# External_Power_Supply.net
KiCad netlist of a schematic drawn in EAGLE
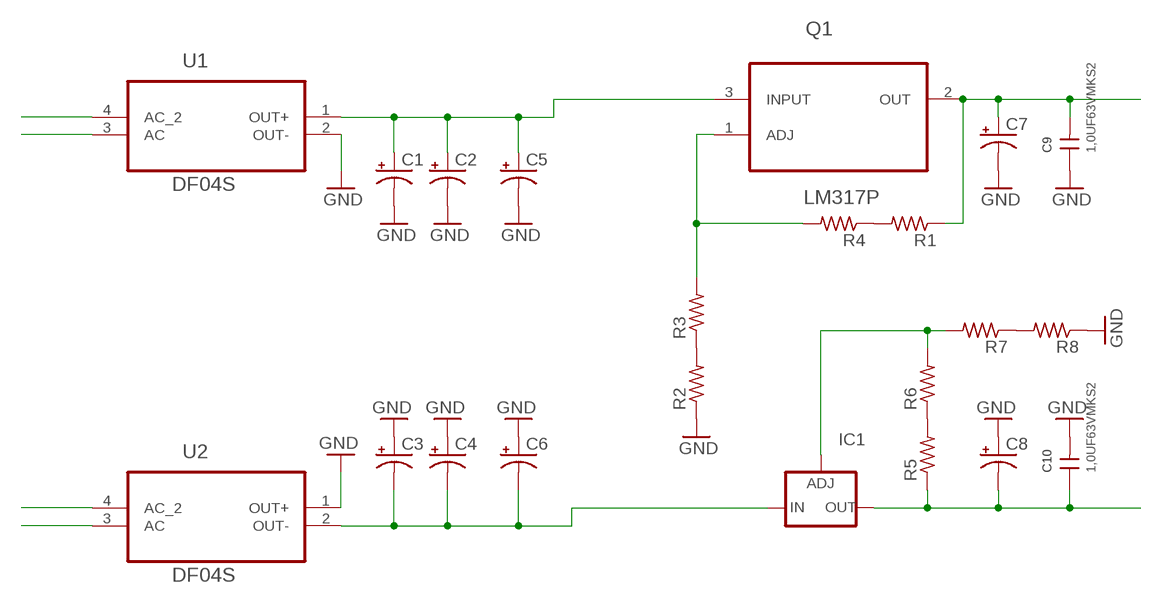
[diagram p0: schematic, sheet 1]

(export (version "E")
  (design (tool "Eeschema 10.0.6"))
  (components
    (comp (ref "C1")
      (value "CPOL-US153CLV-1010")
      (footprint "eagle-import:153CLV-1010")
      (libsource (lib "eagle-import") (part "CPOL-US153CLV-1010"))
    )
    (comp (ref "C2")
      (value "CPOL-US153CLV-1010")
      (footprint "eagle-import:153CLV-1010")
      (libsource (lib "eagle-import") (part "CPOL-US153CLV-1010"))
    )
    (comp (ref "C3")
      (value "CPOL-US153CLV-1010")
      (footprint "eagle-import:153CLV-1010")
      (libsource (lib "eagle-import") (part "CPOL-US153CLV-1010"))
    )
    (comp (ref "C4")
      (value "CPOL-US153CLV-1010")
      (footprint "eagle-import:153CLV-1010")
      (libsource (lib "eagle-import") (part "CPOL-US153CLV-1010"))
    )
    (comp (ref "C5")
      (value "CPOL-USF")
      (footprint "eagle-import:PANASONIC_F")
      (libsource (lib "eagle-import") (part "CPOL-USF"))
    )
    (comp (ref "C6")
      (value "CPOL-USF")
      (footprint "eagle-import:PANASONIC_F")
      (libsource (lib "eagle-import") (part "CPOL-USF"))
    )
    (comp (ref "C7")
      (value "CPOL-USF")
      (footprint "eagle-import:PANASONIC_F")
      (libsource (lib "eagle-import") (part "CPOL-USF"))
    )
    (comp (ref "C8")
      (value "CPOL-USF")
      (footprint "eagle-import:PANASONIC_F")
      (libsource (lib "eagle-import") (part "CPOL-USF"))
    )
    (comp (ref "C9")
      (value "1,0UF63VMKS2")
      (footprint "eagle-import:5,0X10,0RM5,0")
      (libsource (lib "eagle-import") (part "1,0UF63VMKS2"))
    )
    (comp (ref "C10")
      (value "1,0UF63VMKS2")
      (footprint "eagle-import:5,0X10,0RM5,0")
      (libsource (lib "eagle-import") (part "1,0UF63VMKS2"))
    )
    (comp (ref "IC1")
      (value "LM337TS")
      (footprint "eagle-import:337TS")
      (libsource (lib "eagle-import") (part "LM337TS"))
    )
    (comp (ref "Q1")
      (value "LM317P")
      (footprint "eagle-import:TO254P450X1020X2000-3P")
      (libsource (lib "eagle-import") (part "LM317P"))
    )
    (comp (ref "R1")
      (value "R-US_R0603")
      (footprint "eagle-import:R0603")
      (libsource (lib "eagle-import") (part "R-US_R0603"))
    )
    (comp (ref "R2")
      (value "R-US_R0603")
      (footprint "eagle-import:R0603")
      (libsource (lib "eagle-import") (part "R-US_R0603"))
    )
    (comp (ref "R3")
      (value "R-US_R0603")
      (footprint "eagle-import:R0603")
      (libsource (lib "eagle-import") (part "R-US_R0603"))
    )
    (comp (ref "R4")
      (value "R-US_R0603")
      (footprint "eagle-import:R0603")
      (libsource (lib "eagle-import") (part "R-US_R0603"))
    )
    (comp (ref "R5")
      (value "R-US_R0603")
      (footprint "eagle-import:R0603")
      (libsource (lib "eagle-import") (part "R-US_R0603"))
    )
    (comp (ref "R6")
      (value "R-US_R0603")
      (footprint "eagle-import:R0603")
      (libsource (lib "eagle-import") (part "R-US_R0603"))
    )
    (comp (ref "R7")
      (value "R-US_R0603")
      (footprint "eagle-import:R0603")
      (libsource (lib "eagle-import") (part "R-US_R0603"))
    )
    (comp (ref "R8")
      (value "R-US_R0603")
      (footprint "eagle-import:R0603")
      (libsource (lib "eagle-import") (part "R-US_R0603"))
    )
    (comp (ref "U1")
      (value "DF04S")
      (footprint "eagle-import:SOT508P985X260-4N")
      (libsource (lib "eagle-import") (part "DF04S"))
    )
    (comp (ref "U2")
      (value "DF04S")
      (footprint "eagle-import:SOT508P985X260-4N")
      (libsource (lib "eagle-import") (part "DF04S"))
    )
  )
  (nets
    (net (code "1") (name "GND") (class "Default")
      (node (ref "C1") (pin "-") (pinfunction "-_-") (pintype "passive"))
      (node (ref "C10") (pin "2") (pinfunction "2_2") (pintype "passive"))
      (node (ref "C2") (pin "-") (pinfunction "-_-") (pintype "passive"))
      (node (ref "C3") (pin "+") (pinfunction "+_+") (pintype "passive"))
      (node (ref "C4") (pin "+") (pinfunction "+_+") (pintype "passive"))
      (node (ref "C5") (pin "-") (pinfunction "-_-") (pintype "passive"))
      (node (ref "C6") (pin "+") (pinfunction "+_+") (pintype "passive"))
      (node (ref "C7") (pin "-") (pinfunction "-_-") (pintype "passive"))
      (node (ref "C8") (pin "+") (pinfunction "+_+") (pintype "passive"))
      (node (ref "C9") (pin "1") (pinfunction "1_1") (pintype "passive"))
      (node (ref "R2") (pin "1") (pinfunction "1_1") (pintype "passive"))
      (node (ref "R8") (pin "1") (pinfunction "1_1") (pintype "passive"))
      (node (ref "U1") (pin "2") (pinfunction "OUT-_2") (pintype "output"))
      (node (ref "U2") (pin "1") (pinfunction "OUT+_1") (pintype "output"))
    )
    (net (code "2") (name "Net-(IC1-ADJ)") (class "Default")
      (node (ref "IC1") (pin "1") (pinfunction "ADJ_1") (pintype "input"))
      (node (ref "R6") (pin "2") (pinfunction "2_2") (pintype "passive"))
      (node (ref "R7") (pin "2") (pinfunction "2_2") (pintype "passive"))
    )
    (net (code "3") (name "Net-(IC1-IN)") (class "Default")
      (node (ref "C3") (pin "-") (pinfunction "-_-") (pintype "passive"))
      (node (ref "C4") (pin "-") (pinfunction "-_-") (pintype "passive"))
      (node (ref "C6") (pin "-") (pinfunction "-_-") (pintype "passive"))
      (node (ref "IC1") (pin "2") (pinfunction "IN_2") (pintype "input"))
      (node (ref "U2") (pin "2") (pinfunction "OUT-_2") (pintype "output"))
    )
    (net (code "4") (name "Net-(IC1-OUT)") (class "Default")
      (node (ref "C10") (pin "1") (pinfunction "1_1") (pintype "passive"))
      (node (ref "C8") (pin "-") (pinfunction "-_-") (pintype "passive"))
      (node (ref "IC1") (pin "3") (pinfunction "OUT_3") (pintype "passive"))
      (node (ref "R5") (pin "1") (pinfunction "1_1") (pintype "passive"))
    )
    (net (code "5") (name "Net-(Q1-ADJ)") (class "Default")
      (node (ref "Q1") (pin "1") (pinfunction "ADJ_1") (pintype "input"))
      (node (ref "R3") (pin "2") (pinfunction "2_2") (pintype "passive"))
      (node (ref "R4") (pin "2") (pinfunction "2_2") (pintype "passive"))
    )
    (net (code "6") (name "Net-(Q1-INPUT)") (class "Default")
      (node (ref "C1") (pin "+") (pinfunction "+_+") (pintype "passive"))
      (node (ref "C2") (pin "+") (pinfunction "+_+") (pintype "passive"))
      (node (ref "C5") (pin "+") (pinfunction "+_+") (pintype "passive"))
      (node (ref "Q1") (pin "3") (pinfunction "INPUT_3") (pintype "input"))
      (node (ref "U1") (pin "1") (pinfunction "OUT+_1") (pintype "output"))
    )
    (net (code "7") (name "Net-(Q1-OUT)") (class "Default")
      (node (ref "C7") (pin "+") (pinfunction "+_+") (pintype "passive"))
      (node (ref "C9") (pin "2") (pinfunction "2_2") (pintype "passive"))
      (node (ref "Q1") (pin "2") (pinfunction "OUT_2") (pintype "output"))
      (node (ref "R1") (pin "1") (pinfunction "1_1") (pintype "passive"))
    )
    (net (code "8") (name "Net-(R1-Pad2)") (class "Default")
      (node (ref "R1") (pin "2") (pinfunction "2_2") (pintype "passive"))
      (node (ref "R4") (pin "1") (pinfunction "1_1") (pintype "passive"))
    )
    (net (code "9") (name "Net-(R2-Pad2)") (class "Default")
      (node (ref "R2") (pin "2") (pinfunction "2_2") (pintype "passive"))
      (node (ref "R3") (pin "1") (pinfunction "1_1") (pintype "passive"))
    )
    (net (code "10") (name "Net-(R5-Pad2)") (class "Default")
      (node (ref "R5") (pin "2") (pinfunction "2_2") (pintype "passive"))
      (node (ref "R6") (pin "1") (pinfunction "1_1") (pintype "passive"))
    )
    (net (code "11") (name "Net-(R7-Pad1)") (class "Default")
      (node (ref "R7") (pin "1") (pinfunction "1_1") (pintype "passive"))
      (node (ref "R8") (pin "2") (pinfunction "2_2") (pintype "passive"))
    )
    (net (code "12") (name "unconnected-(U1-AC-Pad3)") (class "Default")
      (node (ref "U1") (pin "3") (pinfunction "AC_3") (pintype "input"))
    )
    (net (code "13") (name "unconnected-(U1-AC_2-Pad4)") (class "Default")
      (node (ref "U1") (pin "4") (pinfunction "AC_2_4") (pintype "input"))
    )
    (net (code "14") (name "unconnected-(U2-AC-Pad3)") (class "Default")
      (node (ref "U2") (pin "3") (pinfunction "AC_3") (pintype "input"))
    )
    (net (code "15") (name "unconnected-(U2-AC_2-Pad4)") (class "Default")
      (node (ref "U2") (pin "4") (pinfunction "AC_2_4") (pintype "input"))
    )
  )
)
